# modulation.net
KiCad netlist of a schematic drawn in EAGLE
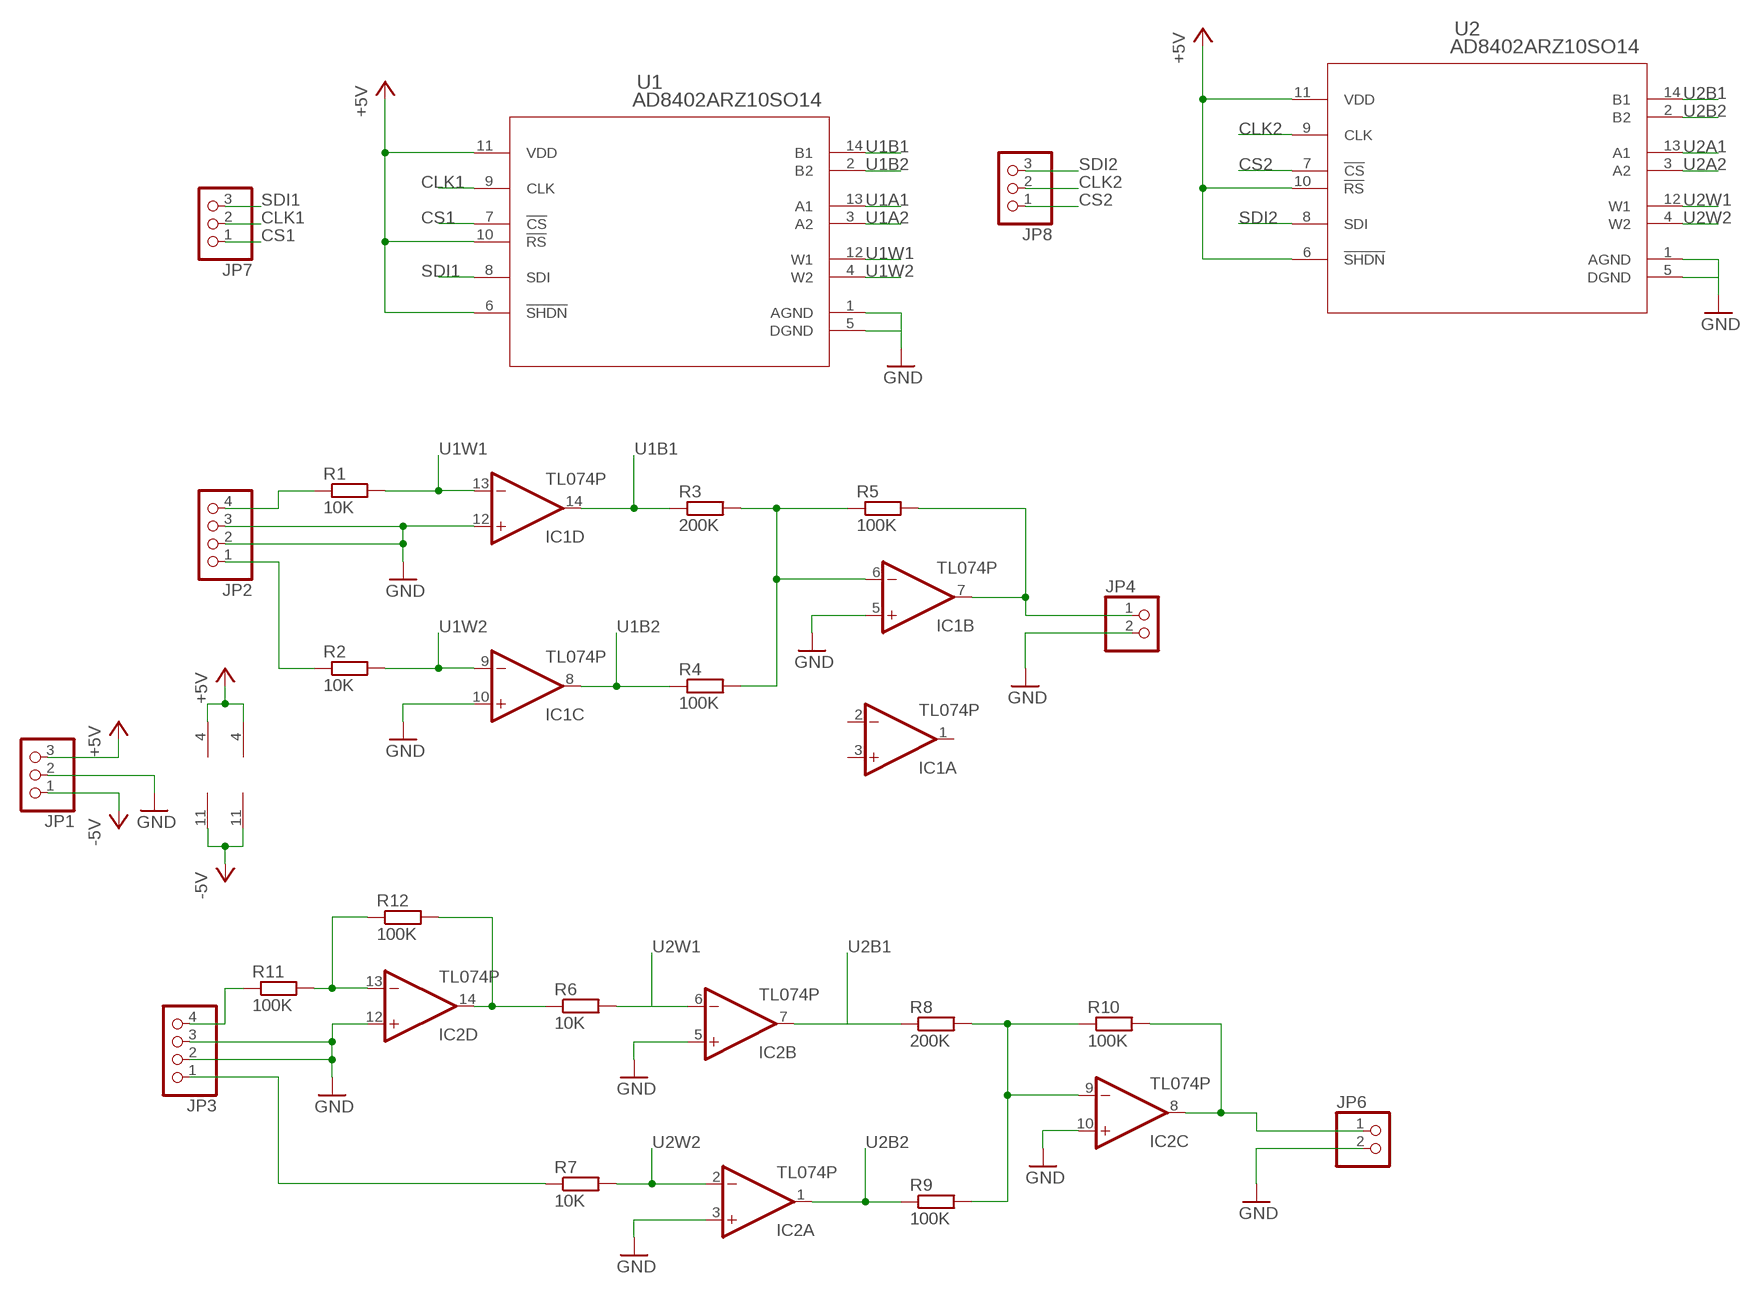
[diagram p0: schematic, sheet 1]

(export (version "E")
  (design (tool "Eeschema 10.0.6"))
  (components
    (comp (ref "IC1")
      (value "TL074P")
      (footprint "eagle-import:DIL14")
      (libsource (lib "eagle-import") (part "TL074P"))
    )
    (comp (ref "IC2")
      (value "TL074P")
      (footprint "eagle-import:DIL14")
      (libsource (lib "eagle-import") (part "TL074P"))
    )
    (comp (ref "JP1")
      (value "PINHD-1X3")
      (footprint "eagle-import:1X03")
      (libsource (lib "eagle-import") (part "PINHD-1X3"))
    )
    (comp (ref "JP2")
      (value "PINHD-1X4")
      (footprint "eagle-import:1X04")
      (libsource (lib "eagle-import") (part "PINHD-1X4"))
    )
    (comp (ref "JP3")
      (value "PINHD-1X4")
      (footprint "eagle-import:1X04")
      (libsource (lib "eagle-import") (part "PINHD-1X4"))
    )
    (comp (ref "JP4")
      (value "PINHD-1X2")
      (footprint "eagle-import:1X02")
      (libsource (lib "eagle-import") (part "PINHD-1X2"))
    )
    (comp (ref "JP6")
      (value "PINHD-1X2")
      (footprint "eagle-import:1X02")
      (libsource (lib "eagle-import") (part "PINHD-1X2"))
    )
    (comp (ref "JP7")
      (value "PINHD-1X3")
      (footprint "eagle-import:1X03")
      (libsource (lib "eagle-import") (part "PINHD-1X3"))
    )
    (comp (ref "JP8")
      (value "PINHD-1X3")
      (footprint "eagle-import:1X03")
      (libsource (lib "eagle-import") (part "PINHD-1X3"))
    )
    (comp (ref "R1")
      (value "10K")
      (footprint "eagle-import:0207_7")
      (libsource (lib "eagle-import") (part "R-EU_0207/7"))
    )
    (comp (ref "R2")
      (value "10K")
      (footprint "eagle-import:0207_7")
      (libsource (lib "eagle-import") (part "R-EU_0207/7"))
    )
    (comp (ref "R3")
      (value "200K")
      (footprint "eagle-import:0207_7")
      (libsource (lib "eagle-import") (part "R-EU_0207/7"))
    )
    (comp (ref "R4")
      (value "100K")
      (footprint "eagle-import:0207_7")
      (libsource (lib "eagle-import") (part "R-EU_0207/7"))
    )
    (comp (ref "R5")
      (value "100K")
      (footprint "eagle-import:0207_7")
      (libsource (lib "eagle-import") (part "R-EU_0207/7"))
    )
    (comp (ref "R6")
      (value "10K")
      (footprint "eagle-import:0207_7")
      (libsource (lib "eagle-import") (part "R-EU_0207/7"))
    )
    (comp (ref "R7")
      (value "10K")
      (footprint "eagle-import:0207_7")
      (libsource (lib "eagle-import") (part "R-EU_0207/7"))
    )
    (comp (ref "R8")
      (value "200K")
      (footprint "eagle-import:0207_7")
      (libsource (lib "eagle-import") (part "R-EU_0207/7"))
    )
    (comp (ref "R9")
      (value "100K")
      (footprint "eagle-import:0207_7")
      (libsource (lib "eagle-import") (part "R-EU_0207/7"))
    )
    (comp (ref "R10")
      (value "100K")
      (footprint "eagle-import:0207_7")
      (libsource (lib "eagle-import") (part "R-EU_0207/7"))
    )
    (comp (ref "R11")
      (value "100K")
      (footprint "eagle-import:0207_7")
      (libsource (lib "eagle-import") (part "R-EU_0207/7"))
    )
    (comp (ref "R12")
      (value "100K")
      (footprint "eagle-import:0207_7")
      (libsource (lib "eagle-import") (part "R-EU_0207/7"))
    )
    (comp (ref "U1")
      (value "AD8402ARZ10SO14")
      (footprint "eagle-import:SO14")
      (libsource (lib "eagle-import") (part "AD8402ARZ10SO14"))
    )
    (comp (ref "U2")
      (value "AD8402ARZ10SO14")
      (footprint "eagle-import:SO14")
      (libsource (lib "eagle-import") (part "AD8402ARZ10SO14"))
    )
  )
  (nets
    (net (code "1") (name "+5V") (class "Default")
      (node (ref "IC1") (pin "4") (pinfunction "V+_4") (pintype "power_in"))
      (node (ref "IC2") (pin "4") (pinfunction "V+_4") (pintype "power_in"))
      (node (ref "JP1") (pin "3") (pinfunction "3_3") (pintype "passive"))
      (node (ref "U1") (pin "10") (pinfunction "~{RS}_10") (pintype "passive"))
      (node (ref "U1") (pin "11") (pinfunction "VDD_11") (pintype "passive"))
      (node (ref "U1") (pin "6") (pinfunction "~{SHDN}_6") (pintype "passive"))
      (node (ref "U2") (pin "10") (pinfunction "~{RS}_10") (pintype "passive"))
      (node (ref "U2") (pin "11") (pinfunction "VDD_11") (pintype "passive"))
      (node (ref "U2") (pin "6") (pinfunction "~{SHDN}_6") (pintype "passive"))
    )
    (net (code "2") (name "-5V") (class "Default")
      (node (ref "IC1") (pin "11") (pinfunction "V-_11") (pintype "power_in"))
      (node (ref "IC2") (pin "11") (pinfunction "V-_11") (pintype "power_in"))
      (node (ref "JP1") (pin "1") (pinfunction "1_1") (pintype "passive"))
    )
    (net (code "3") (name "/CLK1") (class "Default")
      (node (ref "JP7") (pin "2") (pinfunction "2_2") (pintype "passive"))
      (node (ref "U1") (pin "9") (pinfunction "CLK_9") (pintype "passive"))
    )
    (net (code "4") (name "/CLK2") (class "Default")
      (node (ref "JP8") (pin "2") (pinfunction "2_2") (pintype "passive"))
      (node (ref "U2") (pin "9") (pinfunction "CLK_9") (pintype "passive"))
    )
    (net (code "5") (name "/CS1") (class "Default")
      (node (ref "JP7") (pin "1") (pinfunction "1_1") (pintype "passive"))
      (node (ref "U1") (pin "7") (pinfunction "~{CS}_7") (pintype "passive"))
    )
    (net (code "6") (name "/CS2") (class "Default")
      (node (ref "JP8") (pin "1") (pinfunction "1_1") (pintype "passive"))
      (node (ref "U2") (pin "7") (pinfunction "~{CS}_7") (pintype "passive"))
    )
    (net (code "7") (name "/SDI1") (class "Default")
      (node (ref "JP7") (pin "3") (pinfunction "3_3") (pintype "passive"))
      (node (ref "U1") (pin "8") (pinfunction "SDI_8") (pintype "passive"))
    )
    (net (code "8") (name "/SDI2") (class "Default")
      (node (ref "JP8") (pin "3") (pinfunction "3_3") (pintype "passive"))
      (node (ref "U2") (pin "8") (pinfunction "SDI_8") (pintype "passive"))
    )
    (net (code "9") (name "/U1A1") (class "Default")
      (node (ref "U1") (pin "13") (pinfunction "A1_13") (pintype "passive"))
    )
    (net (code "10") (name "/U1A2") (class "Default")
      (node (ref "U1") (pin "3") (pinfunction "A2_3") (pintype "passive"))
    )
    (net (code "11") (name "/U1B1") (class "Default")
      (node (ref "IC1") (pin "14") (pinfunction "OUT_14") (pintype "output"))
      (node (ref "R3") (pin "1") (pinfunction "1_1") (pintype "passive"))
      (node (ref "U1") (pin "14") (pinfunction "B1_14") (pintype "passive"))
    )
    (net (code "12") (name "/U1B2") (class "Default")
      (node (ref "IC1") (pin "8") (pinfunction "OUT_8") (pintype "output"))
      (node (ref "R4") (pin "1") (pinfunction "1_1") (pintype "passive"))
      (node (ref "U1") (pin "2") (pinfunction "B2_2") (pintype "passive"))
    )
    (net (code "13") (name "/U1W1") (class "Default")
      (node (ref "IC1") (pin "13") (pinfunction "-IN_13") (pintype "input"))
      (node (ref "R1") (pin "2") (pinfunction "2_2") (pintype "passive"))
      (node (ref "U1") (pin "12") (pinfunction "W1_12") (pintype "passive"))
    )
    (net (code "14") (name "/U1W2") (class "Default")
      (node (ref "IC1") (pin "9") (pinfunction "-IN_9") (pintype "input"))
      (node (ref "R2") (pin "2") (pinfunction "2_2") (pintype "passive"))
      (node (ref "U1") (pin "4") (pinfunction "W2_4") (pintype "passive"))
    )
    (net (code "15") (name "/U2A1") (class "Default")
      (node (ref "U2") (pin "13") (pinfunction "A1_13") (pintype "passive"))
    )
    (net (code "16") (name "/U2A2") (class "Default")
      (node (ref "U2") (pin "3") (pinfunction "A2_3") (pintype "passive"))
    )
    (net (code "17") (name "/U2B1") (class "Default")
      (node (ref "IC2") (pin "7") (pinfunction "OUT_7") (pintype "output"))
      (node (ref "R8") (pin "1") (pinfunction "1_1") (pintype "passive"))
      (node (ref "U2") (pin "14") (pinfunction "B1_14") (pintype "passive"))
    )
    (net (code "18") (name "/U2B2") (class "Default")
      (node (ref "IC2") (pin "1") (pinfunction "OUT_1") (pintype "output"))
      (node (ref "R9") (pin "1") (pinfunction "1_1") (pintype "passive"))
      (node (ref "U2") (pin "2") (pinfunction "B2_2") (pintype "passive"))
    )
    (net (code "19") (name "/U2W1") (class "Default")
      (node (ref "IC2") (pin "6") (pinfunction "-IN_6") (pintype "input"))
      (node (ref "R6") (pin "2") (pinfunction "2_2") (pintype "passive"))
      (node (ref "U2") (pin "12") (pinfunction "W1_12") (pintype "passive"))
    )
    (net (code "20") (name "/U2W2") (class "Default")
      (node (ref "IC2") (pin "2") (pinfunction "-IN_2") (pintype "input"))
      (node (ref "R7") (pin "2") (pinfunction "2_2") (pintype "passive"))
      (node (ref "U2") (pin "4") (pinfunction "W2_4") (pintype "passive"))
    )
    (net (code "21") (name "GND") (class "Default")
      (node (ref "IC1") (pin "10") (pinfunction "+IN_10") (pintype "input"))
      (node (ref "IC1") (pin "12") (pinfunction "+IN_12") (pintype "input"))
      (node (ref "IC1") (pin "5") (pinfunction "+IN_5") (pintype "input"))
      (node (ref "IC2") (pin "10") (pinfunction "+IN_10") (pintype "input"))
      (node (ref "IC2") (pin "12") (pinfunction "+IN_12") (pintype "input"))
      (node (ref "IC2") (pin "3") (pinfunction "+IN_3") (pintype "input"))
      (node (ref "IC2") (pin "5") (pinfunction "+IN_5") (pintype "input"))
      (node (ref "JP1") (pin "2") (pinfunction "2_2") (pintype "passive"))
      (node (ref "JP2") (pin "2") (pinfunction "2_2") (pintype "passive"))
      (node (ref "JP2") (pin "3") (pinfunction "3_3") (pintype "passive"))
      (node (ref "JP3") (pin "2") (pinfunction "2_2") (pintype "passive"))
      (node (ref "JP3") (pin "3") (pinfunction "3_3") (pintype "passive"))
      (node (ref "JP4") (pin "2") (pinfunction "2_2") (pintype "passive"))
      (node (ref "JP6") (pin "2") (pinfunction "2_2") (pintype "passive"))
      (node (ref "U1") (pin "1") (pinfunction "AGND_1") (pintype "passive"))
      (node (ref "U1") (pin "5") (pinfunction "DGND_5") (pintype "passive"))
      (node (ref "U2") (pin "1") (pinfunction "AGND_1") (pintype "passive"))
      (node (ref "U2") (pin "5") (pinfunction "DGND_5") (pintype "passive"))
    )
    (net (code "22") (name "Net-(IC1B--IN)") (class "Default")
      (node (ref "IC1") (pin "6") (pinfunction "-IN_6") (pintype "input"))
      (node (ref "R3") (pin "2") (pinfunction "2_2") (pintype "passive"))
      (node (ref "R4") (pin "2") (pinfunction "2_2") (pintype "passive"))
      (node (ref "R5") (pin "1") (pinfunction "1_1") (pintype "passive"))
    )
    (net (code "23") (name "Net-(IC1B-OUT)") (class "Default")
      (node (ref "IC1") (pin "7") (pinfunction "OUT_7") (pintype "output"))
      (node (ref "JP4") (pin "1") (pinfunction "1_1") (pintype "passive"))
      (node (ref "R5") (pin "2") (pinfunction "2_2") (pintype "passive"))
    )
    (net (code "24") (name "Net-(IC2C--IN)") (class "Default")
      (node (ref "IC2") (pin "9") (pinfunction "-IN_9") (pintype "input"))
      (node (ref "R10") (pin "1") (pinfunction "1_1") (pintype "passive"))
      (node (ref "R8") (pin "2") (pinfunction "2_2") (pintype "passive"))
      (node (ref "R9") (pin "2") (pinfunction "2_2") (pintype "passive"))
    )
    (net (code "25") (name "Net-(IC2C-OUT)") (class "Default")
      (node (ref "IC2") (pin "8") (pinfunction "OUT_8") (pintype "output"))
      (node (ref "JP6") (pin "1") (pinfunction "1_1") (pintype "passive"))
      (node (ref "R10") (pin "2") (pinfunction "2_2") (pintype "passive"))
    )
    (net (code "26") (name "Net-(IC2D--IN)") (class "Default")
      (node (ref "IC2") (pin "13") (pinfunction "-IN_13") (pintype "input"))
      (node (ref "R11") (pin "2") (pinfunction "2_2") (pintype "passive"))
      (node (ref "R12") (pin "1") (pinfunction "1_1") (pintype "passive"))
    )
    (net (code "27") (name "Net-(IC2D-OUT)") (class "Default")
      (node (ref "IC2") (pin "14") (pinfunction "OUT_14") (pintype "output"))
      (node (ref "R12") (pin "2") (pinfunction "2_2") (pintype "passive"))
      (node (ref "R6") (pin "1") (pinfunction "1_1") (pintype "passive"))
    )
    (net (code "28") (name "Net-(JP2-Pad1)") (class "Default")
      (node (ref "JP2") (pin "1") (pinfunction "1_1") (pintype "passive"))
      (node (ref "R2") (pin "1") (pinfunction "1_1") (pintype "passive"))
    )
    (net (code "29") (name "Net-(JP2-Pad4)") (class "Default")
      (node (ref "JP2") (pin "4") (pinfunction "4_4") (pintype "passive"))
      (node (ref "R1") (pin "1") (pinfunction "1_1") (pintype "passive"))
    )
    (net (code "30") (name "Net-(JP3-Pad1)") (class "Default")
      (node (ref "JP3") (pin "1") (pinfunction "1_1") (pintype "passive"))
      (node (ref "R7") (pin "1") (pinfunction "1_1") (pintype "passive"))
    )
    (net (code "31") (name "Net-(JP3-Pad4)") (class "Default")
      (node (ref "JP3") (pin "4") (pinfunction "4_4") (pintype "passive"))
      (node (ref "R11") (pin "1") (pinfunction "1_1") (pintype "passive"))
    )
    (net (code "32") (name "unconnected-(IC1A-+IN-Pad3)") (class "Default")
      (node (ref "IC1") (pin "3") (pinfunction "+IN_3") (pintype "input"))
    )
    (net (code "33") (name "unconnected-(IC1A--IN-Pad2)") (class "Default")
      (node (ref "IC1") (pin "2") (pinfunction "-IN_2") (pintype "input"))
    )
    (net (code "34") (name "unconnected-(IC1A-OUT-Pad1)") (class "Default")
      (node (ref "IC1") (pin "1") (pinfunction "OUT_1") (pintype "output"))
    )
  )
)
